# macropad_synthplug_long.net
KiCad netlist of a schematic drawn in EAGLE
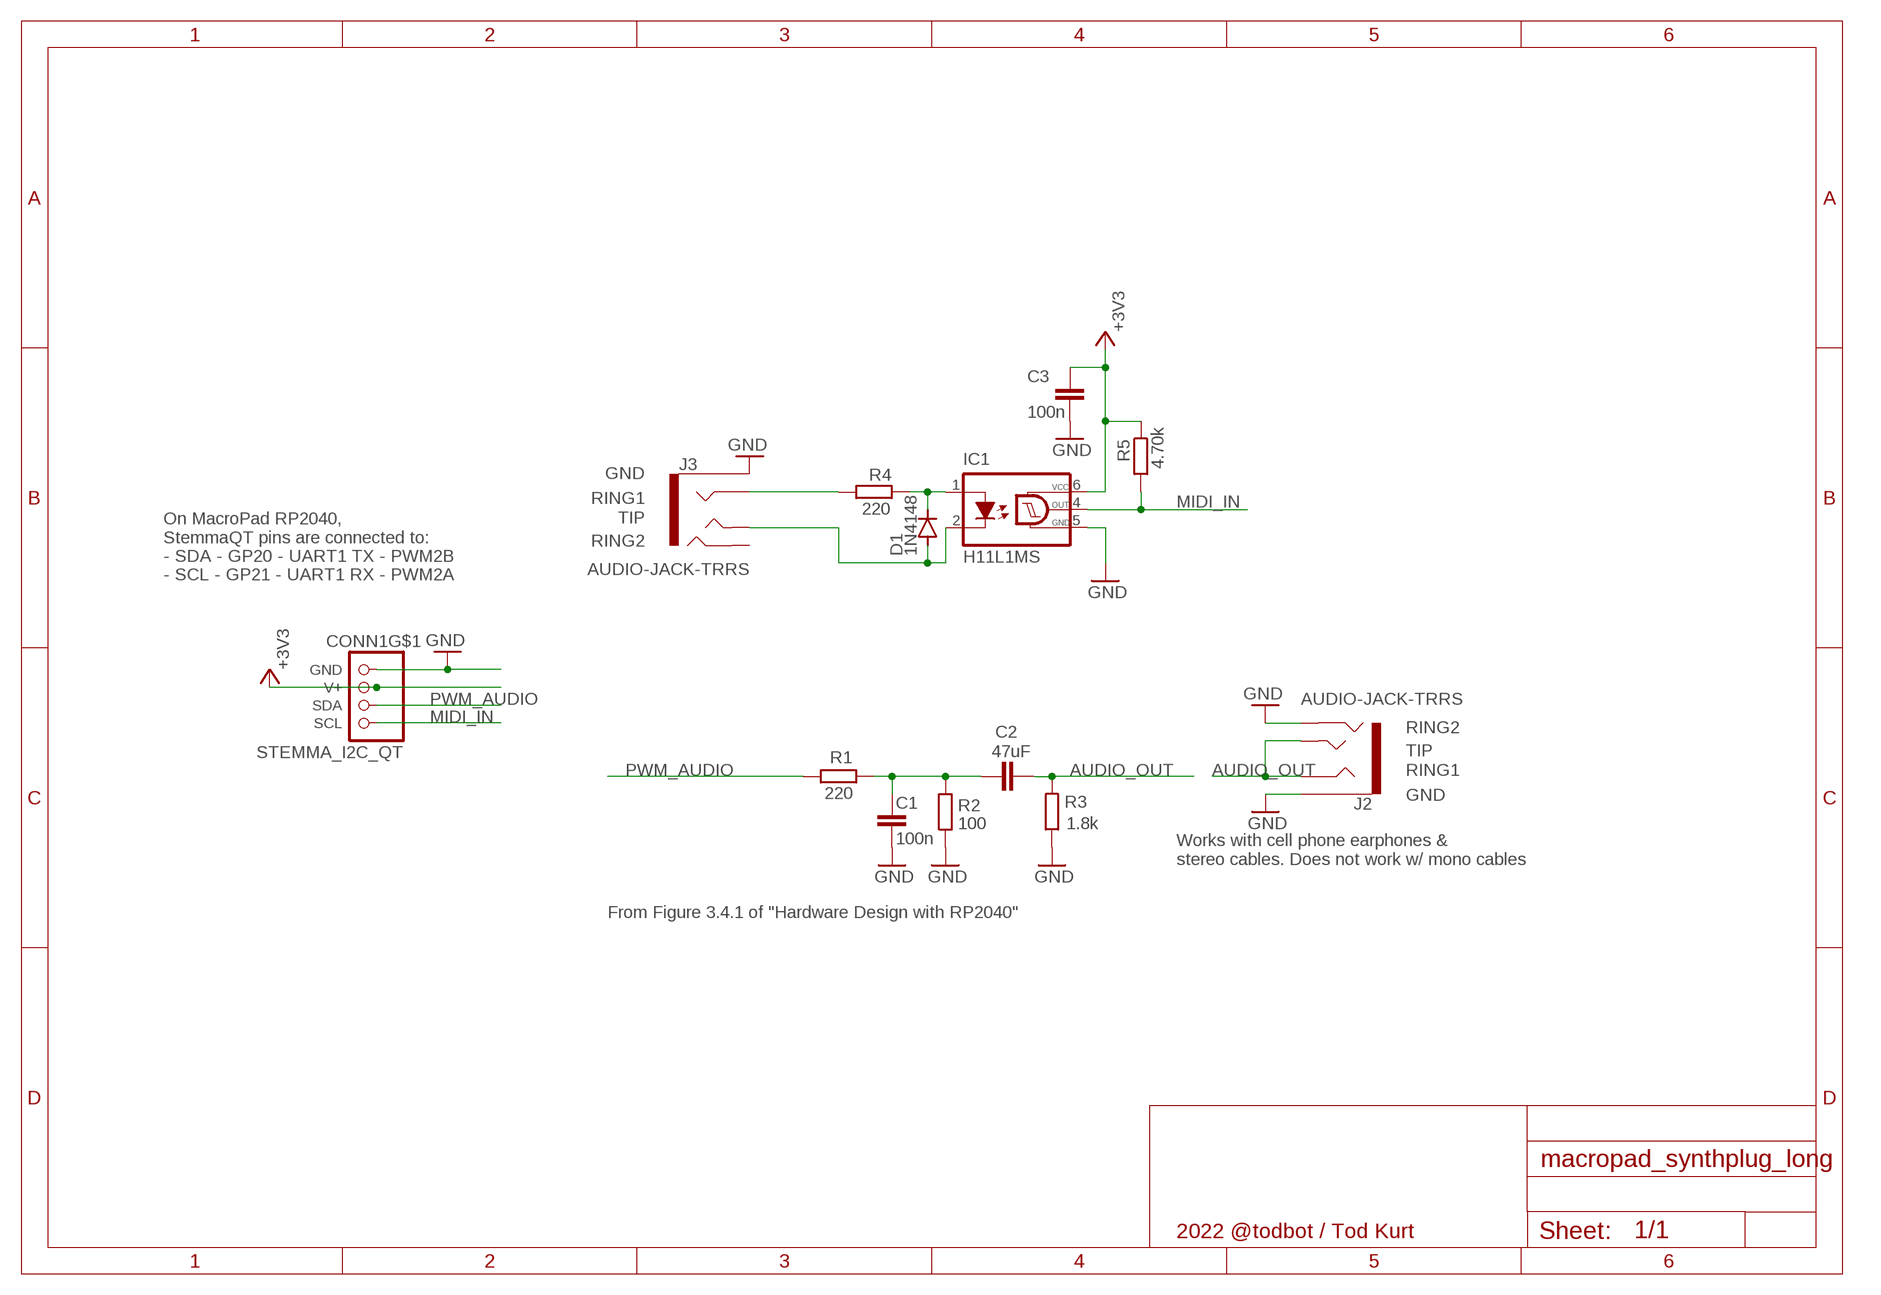
[diagram p0: schematic, sheet 1]

(export (version "E")
  (design (tool "Eeschema 10.0.6"))
  (components
    (comp (ref "C1")
      (value "100n")
      (footprint "eagle-import:C0805")
      (libsource (lib "eagle-import") (part "C-EUC0805"))
    )
    (comp (ref "C2")
      (value "47uF")
      (footprint "eagle-import:C0805")
      (libsource (lib "eagle-import") (part "C-EUC0805"))
    )
    (comp (ref "C3")
      (value "100n")
      (footprint "eagle-import:C0805")
      (libsource (lib "eagle-import") (part "C-EUC0805"))
    )
    (comp (ref "CONN1")
      (value "STEMMA_I2C_QT")
      (footprint "eagle-import:JST_SH4")
      (fields (field (name "MPN") "HC-1.0-4PWT"))
      (libsource (lib "eagle-import") (part "STEMMA_I2C_QT"))
    )
    (comp (ref "D1")
      (value "1N4148")
      (footprint "eagle-import:SOD123")
      (libsource (lib "eagle-import") (part "DIODE-SOD123"))
    )
    (comp (ref "IC1")
      (value "H11L1MS")
      (footprint "eagle-import:DIL6-SMD")
      (libsource (lib "eagle-import") (part "H11LMS1"))
    )
    (comp (ref "J2")
      (value "AUDIO-JACK-TRRS")
      (footprint "eagle-import:PJ-320D_SPARKFUN")
      (fields (field (name "MPN") "PJ-320D") (field (name "LCSC") "C431535"))
      (libsource (lib "eagle-import") (part "AUDIO-JACK-TRRS"))
    )
    (comp (ref "J3")
      (value "AUDIO-JACK-TRRS")
      (footprint "eagle-import:PJ-320D_SPARKFUN")
      (fields (field (name "MPN") "PJ-320D"))
      (libsource (lib "eagle-import") (part "AUDIO-JACK-TRRS"))
    )
    (comp (ref "R1")
      (value "220")
      (footprint "eagle-import:R0805")
      (libsource (lib "eagle-import") (part "R-EU_R0805"))
    )
    (comp (ref "R2")
      (value "100")
      (footprint "eagle-import:R0805")
      (libsource (lib "eagle-import") (part "R-EU_R0805"))
    )
    (comp (ref "R3")
      (value "1.8k")
      (footprint "eagle-import:R0805")
      (libsource (lib "eagle-import") (part "R-EU_R0805"))
    )
    (comp (ref "R4")
      (value "220")
      (footprint "eagle-import:R0805")
      (libsource (lib "eagle-import") (part "R-EU_R0805"))
    )
    (comp (ref "R5")
      (value "4.70k")
      (footprint "eagle-import:R0805")
      (libsource (lib "eagle-import") (part "R-EU_R0805"))
    )
  )
  (nets
    (net (code "1") (name "+3V3") (class "Default")
      (node (ref "C3") (pin "1") (pinfunction "1_1") (pintype "passive"))
      (node (ref "CONN1") (pin "2") (pinfunction "V+_2") (pintype "passive"))
      (node (ref "IC1") (pin "6") (pinfunction "VCC_6") (pintype "power_in"))
      (node (ref "R5") (pin "1") (pinfunction "1_1") (pintype "passive"))
    )
    (net (code "2") (name "/AUDIO_OUT") (class "Default")
      (node (ref "C2") (pin "2") (pinfunction "2_2") (pintype "passive"))
      (node (ref "J2") (pin "RING1") (pinfunction "RING1_RING1") (pintype "bidirectional"))
      (node (ref "J2") (pin "TIP") (pinfunction "TIP_TIP") (pintype "bidirectional"))
      (node (ref "R3") (pin "1") (pinfunction "1_1") (pintype "passive"))
    )
    (net (code "3") (name "/MIDI_IN") (class "Default")
      (node (ref "CONN1") (pin "4") (pinfunction "SCL_4") (pintype "passive"))
      (node (ref "IC1") (pin "4") (pinfunction "OUT_4") (pintype "output"))
      (node (ref "R5") (pin "2") (pinfunction "2_2") (pintype "passive"))
    )
    (net (code "4") (name "/PWM_AUDIO") (class "Default")
      (node (ref "CONN1") (pin "3") (pinfunction "SDA_3") (pintype "passive"))
      (node (ref "R1") (pin "2") (pinfunction "2_2") (pintype "passive"))
    )
    (net (code "5") (name "GND") (class "Default")
      (node (ref "C1") (pin "2") (pinfunction "2_2") (pintype "passive"))
      (node (ref "C3") (pin "2") (pinfunction "2_2") (pintype "passive"))
      (node (ref "CONN1") (pin "1") (pinfunction "GND_1") (pintype "passive"))
      (node (ref "IC1") (pin "5") (pinfunction "GND_5") (pintype "power_in"))
      (node (ref "J2") (pin "EARTH") (pinfunction "EARTH_EARTH") (pintype "bidirectional"))
      (node (ref "J2") (pin "RING2") (pinfunction "RING2_RING2") (pintype "bidirectional"))
      (node (ref "J3") (pin "EARTH") (pinfunction "EARTH_EARTH") (pintype "bidirectional"))
      (node (ref "R2") (pin "1") (pinfunction "1_1") (pintype "passive"))
      (node (ref "R3") (pin "2") (pinfunction "2_2") (pintype "passive"))
    )
    (net (code "6") (name "Net-(C1-Pad1)") (class "Default")
      (node (ref "C1") (pin "1") (pinfunction "1_1") (pintype "passive"))
      (node (ref "C2") (pin "1") (pinfunction "1_1") (pintype "passive"))
      (node (ref "R1") (pin "1") (pinfunction "1_1") (pintype "passive"))
      (node (ref "R2") (pin "2") (pinfunction "2_2") (pintype "passive"))
    )
    (net (code "7") (name "Net-(IC1-A)") (class "Default")
      (node (ref "D1") (pin "C") (pinfunction "C_C") (pintype "passive"))
      (node (ref "IC1") (pin "1") (pinfunction "A_1") (pintype "passive"))
      (node (ref "R4") (pin "1") (pinfunction "1_1") (pintype "passive"))
    )
    (net (code "8") (name "Net-(IC1-C)") (class "Default")
      (node (ref "D1") (pin "A") (pinfunction "A_A") (pintype "passive"))
      (node (ref "IC1") (pin "2") (pinfunction "C_2") (pintype "passive"))
      (node (ref "J3") (pin "TIP") (pinfunction "TIP_TIP") (pintype "bidirectional"))
    )
    (net (code "9") (name "Net-(J3-PadRING1)") (class "Default")
      (node (ref "J3") (pin "RING1") (pinfunction "RING1_RING1") (pintype "bidirectional"))
      (node (ref "R4") (pin "2") (pinfunction "2_2") (pintype "passive"))
    )
    (net (code "10") (name "unconnected-(J3-PadRING2)") (class "Default")
      (node (ref "J3") (pin "RING2") (pinfunction "RING2_RING2") (pintype "bidirectional"))
    )
  )
)
